# nyan-pirate.net
KiCad netlist of a schematic drawn in EAGLE
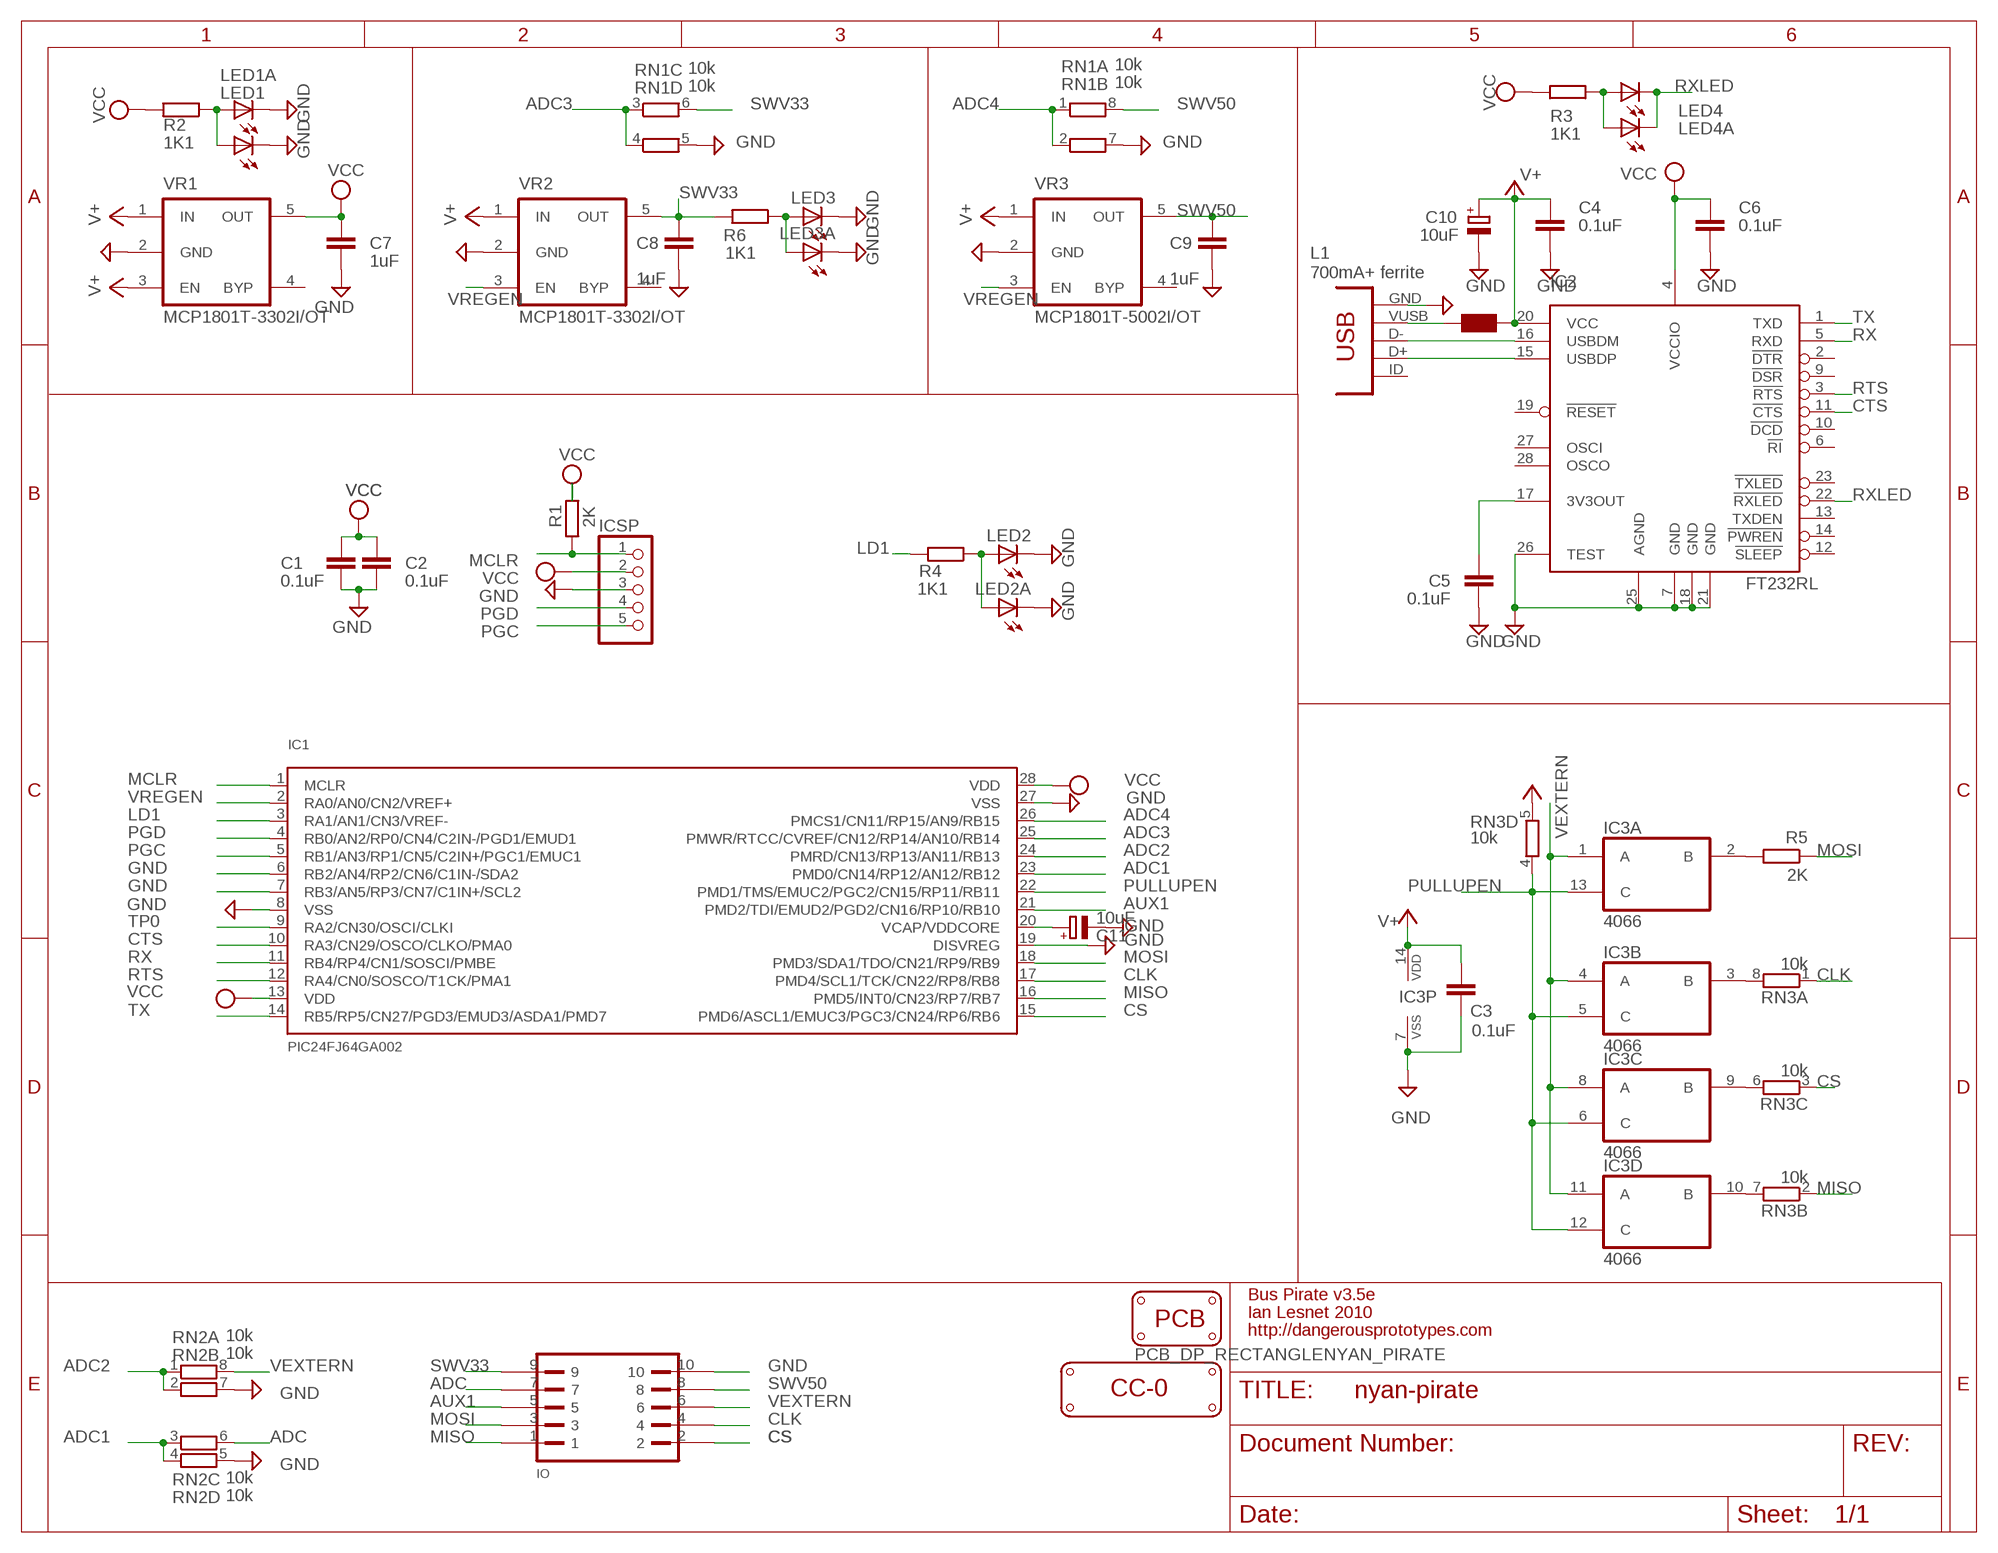
[diagram p0: schematic, sheet 1]

(export (version "E")
  (design (tool "Eeschema 10.0.6"))
  (components
    (comp (ref "C1")
      (value "0.1uF")
      (footprint "eagle-import:C603")
      (libsource (lib "eagle-import") (part "CAPC603"))
    )
    (comp (ref "C2")
      (value "0.1uF")
      (footprint "eagle-import:C603")
      (libsource (lib "eagle-import") (part "CAPC603"))
    )
    (comp (ref "C3")
      (value "0.1uF")
      (footprint "eagle-import:C603")
      (libsource (lib "eagle-import") (part "CAPC603"))
    )
    (comp (ref "C4")
      (value "0.1uF")
      (footprint "eagle-import:C603")
      (libsource (lib "eagle-import") (part "CAPC603"))
    )
    (comp (ref "C5")
      (value "0.1uF")
      (footprint "eagle-import:C603")
      (libsource (lib "eagle-import") (part "CAPC603"))
    )
    (comp (ref "C6")
      (value "0.1uF")
      (footprint "eagle-import:C603")
      (libsource (lib "eagle-import") (part "CAPC603"))
    )
    (comp (ref "C7")
      (value "1uF")
      (footprint "eagle-import:C603")
      (libsource (lib "eagle-import") (part "CAPC603"))
    )
    (comp (ref "C8")
      (value "1uF")
      (footprint "eagle-import:C603")
      (libsource (lib "eagle-import") (part "CAPC603"))
    )
    (comp (ref "C9")
      (value "1uF")
      (footprint "eagle-import:C603")
      (libsource (lib "eagle-import") (part "CAPC603"))
    )
    (comp (ref "C10")
      (value "10uF")
      (footprint "eagle-import:SMC_A")
      (libsource (lib "eagle-import") (part "CPOL-EUSMCA"))
    )
    (comp (ref "C11")
      (value "10uF")
      (footprint "eagle-import:SMC_A")
      (libsource (lib "eagle-import") (part "CPOL-EUSMCA"))
    )
    (comp (ref "IC1")
      (value "PIC24FJ64GA002")
      (footprint "eagle-import:SSOP28")
      (libsource (lib "eagle-import") (part "PIC24FJ64GA002"))
    )
    (comp (ref "IC2")
      (value "FT232RL")
      (footprint "eagle-import:SSOP28")
      (libsource (lib "eagle-import") (part "FT232RL"))
    )
    (comp (ref "IC3")
      (value "4066")
      (footprint "eagle-import:TSSOP14")
      (libsource (lib "eagle-import") (part "4066"))
    )
    (comp (ref "ICSP")
      (value "PINHD-1X5")
      (footprint "eagle-import:1X05")
      (libsource (lib "eagle-import") (part "PINHD-1X5"))
    )
    (comp (ref "IO")
      (value "HEADER2X5-SHRD-PTH-B")
      (footprint "eagle-import:PINSHRD_PTH_2X05B")
      (libsource (lib "eagle-import") (part "HEADER2X5-SHRD-PTH-B"))
    )
    (comp (ref "J1")
      (value "CON-USB-MINI-BUSB1")
      (footprint "eagle-import:CONN_USB_MINI-B")
      (libsource (lib "eagle-import") (part "CON-USB-MINI-BUSB1"))
    )
    (comp (ref "L1")
      (value "700mA+ ferrite")
      (footprint "eagle-import:WE-KI_0805_B")
      (libsource (lib "eagle-import") (part "WE-KIL_0805"))
    )
    (comp (ref "LED1")
      (value "LEDCHIP-LED0805")
      (footprint "eagle-import:CHIP-LED0805")
      (libsource (lib "eagle-import") (part "LEDCHIP-LED0805"))
    )
    (comp (ref "LED1A")
      (value "LEDCHIP-LED0805")
      (footprint "eagle-import:CHIP-LED0805")
      (libsource (lib "eagle-import") (part "LEDCHIP-LED0805"))
    )
    (comp (ref "LED2")
      (value "LEDCHIP-LED0805")
      (footprint "eagle-import:CHIP-LED0805")
      (libsource (lib "eagle-import") (part "LEDCHIP-LED0805"))
    )
    (comp (ref "LED2A")
      (value "LEDCHIP-LED0805")
      (footprint "eagle-import:CHIP-LED0805")
      (libsource (lib "eagle-import") (part "LEDCHIP-LED0805"))
    )
    (comp (ref "LED3")
      (value "LEDCHIP-LED0805")
      (footprint "eagle-import:CHIP-LED0805")
      (libsource (lib "eagle-import") (part "LEDCHIP-LED0805"))
    )
    (comp (ref "LED3A")
      (value "LEDCHIP-LED0805")
      (footprint "eagle-import:CHIP-LED0805")
      (libsource (lib "eagle-import") (part "LEDCHIP-LED0805"))
    )
    (comp (ref "LED4")
      (value "LEDCHIP-LED0805")
      (footprint "eagle-import:CHIP-LED0805")
      (libsource (lib "eagle-import") (part "LEDCHIP-LED0805"))
    )
    (comp (ref "LED4A")
      (value "LEDCHIP-LED0805")
      (footprint "eagle-import:CHIP-LED0805")
      (libsource (lib "eagle-import") (part "LEDCHIP-LED0805"))
    )
    (comp (ref "LOGO1")
      (value "LOGO_CC-0")
      (footprint "eagle-import:LOGO_CC-0")
      (libsource (lib "eagle-import") (part "LOGO_CC-0"))
    )
    (comp (ref "PCB1")
      (value "PCB_DP_RECTANGLENYAN_PIRATE")
      (footprint "eagle-import:NYAN_PIRATE")
      (libsource (lib "eagle-import") (part "PCB_DP_RECTANGLENYAN_PIRATE"))
    )
    (comp (ref "R1")
      (value "2K")
      (footprint "eagle-import:R603")
      (libsource (lib "eagle-import") (part "RESISTORR603"))
    )
    (comp (ref "R2")
      (value "1K1")
      (footprint "eagle-import:R603")
      (libsource (lib "eagle-import") (part "RESISTORR603"))
    )
    (comp (ref "R3")
      (value "1K1")
      (footprint "eagle-import:R603")
      (libsource (lib "eagle-import") (part "RESISTORR603"))
    )
    (comp (ref "R4")
      (value "1K1")
      (footprint "eagle-import:R603")
      (libsource (lib "eagle-import") (part "RESISTORR603"))
    )
    (comp (ref "R5")
      (value "2K")
      (footprint "eagle-import:R603")
      (libsource (lib "eagle-import") (part "RESISTORR603"))
    )
    (comp (ref "R6")
      (value "1K1")
      (footprint "eagle-import:R603")
      (libsource (lib "eagle-import") (part "RESISTORR603"))
    )
    (comp (ref "RN1")
      (value "10k")
      (footprint "eagle-import:RN8P-4R-CRA06S")
      (libsource (lib "eagle-import") (part "RNETWORK"))
    )
    (comp (ref "RN2")
      (value "10k")
      (footprint "eagle-import:RN8P-4R-CRA06S")
      (libsource (lib "eagle-import") (part "RNETWORK"))
    )
    (comp (ref "RN3")
      (value "10k")
      (footprint "eagle-import:RN8P-4R-CRA06S")
      (libsource (lib "eagle-import") (part "RNETWORK"))
    )
    (comp (ref "VR1")
      (value "MCP1801T-3302I/OT")
      (footprint "eagle-import:SOT-23-5")
      (libsource (lib "eagle-import") (part "MIC5205"))
    )
    (comp (ref "VR2")
      (value "MCP1801T-3302I/OT")
      (footprint "eagle-import:SOT-23-5")
      (libsource (lib "eagle-import") (part "MIC5205"))
    )
    (comp (ref "VR3")
      (value "MCP1801T-5002I/OT")
      (footprint "eagle-import:SOT-23-5")
      (libsource (lib "eagle-import") (part "MIC5205"))
    )
  )
  (nets
    (net (code "1") (name "/ADC") (class "Default")
      (node (ref "IO") (pin "7") (pinfunction "7_7") (pintype "passive"))
      (node (ref "RN2") (pin "6") (pinfunction "2_6") (pintype "passive"))
    )
    (net (code "2") (name "/ADC1") (class "Default")
      (node (ref "IC1") (pin "23") (pinfunction "PMD0/CN14/RP12/AN12/RB12_23") (pintype "bidirectional"))
      (node (ref "RN2") (pin "3") (pinfunction "1_3") (pintype "passive"))
      (node (ref "RN2") (pin "4") (pinfunction "1_4") (pintype "passive"))
    )
    (net (code "3") (name "/ADC2") (class "Default")
      (node (ref "IC1") (pin "24") (pinfunction "PMRD/CN13/RP13/AN11/RB13_24") (pintype "bidirectional"))
      (node (ref "RN2") (pin "1") (pinfunction "1_1") (pintype "passive"))
      (node (ref "RN2") (pin "2") (pinfunction "1_2") (pintype "passive"))
    )
    (net (code "4") (name "/ADC3") (class "Default")
      (node (ref "IC1") (pin "25") (pinfunction "PMWR/RTCC/CVREF/CN12/RP14/AN10/RB14_25") (pintype "bidirectional"))
      (node (ref "RN1") (pin "3") (pinfunction "1_3") (pintype "passive"))
      (node (ref "RN1") (pin "4") (pinfunction "1_4") (pintype "passive"))
    )
    (net (code "5") (name "/ADC4") (class "Default")
      (node (ref "IC1") (pin "26") (pinfunction "PMCS1/CN11/RP15/AN9/RB15_26") (pintype "bidirectional"))
      (node (ref "RN1") (pin "1") (pinfunction "1_1") (pintype "passive"))
      (node (ref "RN1") (pin "2") (pinfunction "1_2") (pintype "passive"))
    )
    (net (code "6") (name "/AUX1") (class "Default")
      (node (ref "IC1") (pin "21") (pinfunction "PMD2/TDI/EMUD2/PGD2/CN16/RP10/RB10_21") (pintype "bidirectional"))
      (node (ref "IO") (pin "5") (pinfunction "5_5") (pintype "passive"))
    )
    (net (code "7") (name "/CLK") (class "Default")
      (node (ref "IC1") (pin "17") (pinfunction "PMD4/SCL1/TCK/CN22/RP8/RB8_17") (pintype "bidirectional"))
      (node (ref "IO") (pin "4") (pinfunction "4_4") (pintype "passive"))
      (node (ref "RN3") (pin "1") (pinfunction "1_1") (pintype "passive"))
    )
    (net (code "8") (name "/CS") (class "Default")
      (node (ref "IC1") (pin "15") (pinfunction "PMD6/ASCL1/EMUC3/PGC3/CN24/RP6/RB6_15") (pintype "bidirectional"))
      (node (ref "IO") (pin "2") (pinfunction "2_2") (pintype "passive"))
      (node (ref "RN3") (pin "3") (pinfunction "1_3") (pintype "passive"))
    )
    (net (code "9") (name "/CTS") (class "Default")
      (node (ref "IC1") (pin "10") (pinfunction "RA3/CN29/OSCO/CLKO/PMA0_10") (pintype "bidirectional"))
      (node (ref "IC2") (pin "11") (pinfunction "~{CTS}_11") (pintype "bidirectional"))
    )
    (net (code "10") (name "/LD1") (class "Default")
      (node (ref "IC1") (pin "3") (pinfunction "RA1/AN1/CN3/VREF-_3") (pintype "bidirectional"))
      (node (ref "R4") (pin "2") (pinfunction "2_2") (pintype "passive"))
    )
    (net (code "11") (name "/MCLR") (class "Default")
      (node (ref "IC1") (pin "1") (pinfunction "MCLR_1") (pintype "input"))
      (node (ref "ICSP") (pin "1") (pinfunction "1_1") (pintype "passive"))
      (node (ref "R1") (pin "1") (pinfunction "1_1") (pintype "passive"))
    )
    (net (code "12") (name "/MISO") (class "Default")
      (node (ref "IC1") (pin "16") (pinfunction "PMD5/INT0/CN23/RP7/RB7_16") (pintype "bidirectional"))
      (node (ref "IO") (pin "1") (pinfunction "1_1") (pintype "passive"))
      (node (ref "RN3") (pin "2") (pinfunction "1_2") (pintype "passive"))
    )
    (net (code "13") (name "/MOSI") (class "Default")
      (node (ref "IC1") (pin "18") (pinfunction "PMD3/SDA1/TDO/CN21/RP9/RB9_18") (pintype "bidirectional"))
      (node (ref "IO") (pin "3") (pinfunction "3_3") (pintype "passive"))
      (node (ref "R5") (pin "1") (pinfunction "1_1") (pintype "passive"))
    )
    (net (code "14") (name "/PGC") (class "Default")
      (node (ref "IC1") (pin "5") (pinfunction "RB1/AN3/RP1/CN5/C2IN+/PGC1/EMUC1_5") (pintype "bidirectional"))
      (node (ref "ICSP") (pin "5") (pinfunction "5_5") (pintype "passive"))
    )
    (net (code "15") (name "/PGD") (class "Default")
      (node (ref "IC1") (pin "4") (pinfunction "RB0/AN2/RP0/CN4/C2IN-/PGD1/EMUD1_4") (pintype "bidirectional"))
      (node (ref "ICSP") (pin "4") (pinfunction "4_4") (pintype "passive"))
    )
    (net (code "16") (name "/PULLUPEN") (class "Default")
      (node (ref "IC1") (pin "22") (pinfunction "PMD1/TMS/EMUC2/PGC2/CN15/RP11/RB11_22") (pintype "bidirectional"))
      (node (ref "IC3") (pin "12") (pinfunction "C_12") (pintype "input"))
      (node (ref "IC3") (pin "13") (pinfunction "C_13") (pintype "input"))
      (node (ref "IC3") (pin "5") (pinfunction "C_5") (pintype "input"))
      (node (ref "IC3") (pin "6") (pinfunction "C_6") (pintype "input"))
      (node (ref "RN3") (pin "4") (pinfunction "1_4") (pintype "passive"))
    )
    (net (code "17") (name "/RTS") (class "Default")
      (node (ref "IC1") (pin "12") (pinfunction "RA4/CN0/SOSCO/T1CK/PMA1_12") (pintype "bidirectional"))
      (node (ref "IC2") (pin "3") (pinfunction "~{RTS}_3") (pintype "bidirectional"))
    )
    (net (code "18") (name "/RX") (class "Default")
      (node (ref "IC1") (pin "11") (pinfunction "RB4/RP4/CN1/SOSCI/PMBE_11") (pintype "bidirectional"))
      (node (ref "IC2") (pin "5") (pinfunction "RXD_5") (pintype "bidirectional"))
    )
    (net (code "19") (name "/RXLED") (class "Default")
      (node (ref "IC2") (pin "22") (pinfunction "~{RXLED}_22") (pintype "bidirectional"))
      (node (ref "LED4") (pin "C") (pinfunction "C_C") (pintype "passive"))
      (node (ref "LED4A") (pin "C") (pinfunction "C_C") (pintype "passive"))
    )
    (net (code "20") (name "/SWV33") (class "Default")
      (node (ref "C8") (pin "1") (pinfunction "1_1") (pintype "passive"))
      (node (ref "IO") (pin "9") (pinfunction "9_9") (pintype "passive"))
      (node (ref "R6") (pin "2") (pinfunction "2_2") (pintype "passive"))
      (node (ref "RN1") (pin "6") (pinfunction "2_6") (pintype "passive"))
      (node (ref "VR2") (pin "5") (pinfunction "OUT_5") (pintype "bidirectional"))
    )
    (net (code "21") (name "/SWV50") (class "Default")
      (node (ref "C9") (pin "1") (pinfunction "1_1") (pintype "passive"))
      (node (ref "IO") (pin "8") (pinfunction "8_8") (pintype "passive"))
      (node (ref "RN1") (pin "8") (pinfunction "2_8") (pintype "passive"))
      (node (ref "VR3") (pin "5") (pinfunction "OUT_5") (pintype "bidirectional"))
    )
    (net (code "22") (name "/TP0") (class "Default")
      (node (ref "IC1") (pin "9") (pinfunction "RA2/CN30/OSCI/CLKI_9") (pintype "bidirectional"))
    )
    (net (code "23") (name "/TX") (class "Default")
      (node (ref "IC1") (pin "14") (pinfunction "RB5/RP5/CN27/PGD3/EMUD3/ASDA1/PMD7_14") (pintype "bidirectional"))
      (node (ref "IC2") (pin "1") (pinfunction "TXD_1") (pintype "bidirectional"))
    )
    (net (code "24") (name "/VEXTERN") (class "Default")
      (node (ref "IC3") (pin "1") (pinfunction "A_1") (pintype "tri_state"))
      (node (ref "IC3") (pin "11") (pinfunction "A_11") (pintype "tri_state"))
      (node (ref "IC3") (pin "4") (pinfunction "A_4") (pintype "tri_state"))
      (node (ref "IC3") (pin "8") (pinfunction "A_8") (pintype "tri_state"))
      (node (ref "IO") (pin "6") (pinfunction "6_6") (pintype "passive"))
      (node (ref "RN2") (pin "8") (pinfunction "2_8") (pintype "passive"))
    )
    (net (code "25") (name "/VREGEN") (class "Default")
      (node (ref "IC1") (pin "2") (pinfunction "RA0/AN0/CN2/VREF+_2") (pintype "bidirectional"))
      (node (ref "VR2") (pin "3") (pinfunction "EN_3") (pintype "bidirectional"))
      (node (ref "VR3") (pin "3") (pinfunction "EN_3") (pintype "bidirectional"))
    )
    (net (code "26") (name "GND") (class "Default")
      (node (ref "C1") (pin "2") (pinfunction "2_2") (pintype "passive"))
      (node (ref "C10") (pin "-") (pinfunction "-_-") (pintype "passive"))
      (node (ref "C11") (pin "-") (pinfunction "-_-") (pintype "passive"))
      (node (ref "C2") (pin "2") (pinfunction "2_2") (pintype "passive"))
      (node (ref "C3") (pin "2") (pinfunction "2_2") (pintype "passive"))
      (node (ref "C4") (pin "2") (pinfunction "2_2") (pintype "passive"))
      (node (ref "C5") (pin "2") (pinfunction "2_2") (pintype "passive"))
      (node (ref "C6") (pin "2") (pinfunction "2_2") (pintype "passive"))
      (node (ref "C7") (pin "2") (pinfunction "2_2") (pintype "passive"))
      (node (ref "C8") (pin "2") (pinfunction "2_2") (pintype "passive"))
      (node (ref "C9") (pin "2") (pinfunction "2_2") (pintype "passive"))
      (node (ref "IC1") (pin "19") (pinfunction "DISVREG_19") (pintype "power_in"))
      (node (ref "IC1") (pin "27") (pinfunction "VSS_27") (pintype "power_in"))
      (node (ref "IC1") (pin "6") (pinfunction "RB2/AN4/RP2/CN6/C1IN-/SDA2_6") (pintype "bidirectional"))
      (node (ref "IC1") (pin "7") (pinfunction "RB3/AN5/RP3/CN7/C1IN+/SCL2_7") (pintype "bidirectional"))
      (node (ref "IC1") (pin "8") (pinfunction "VSS_8") (pintype "power_in"))
      (node (ref "IC2") (pin "18") (pinfunction "GND_18") (pintype "bidirectional"))
      (node (ref "IC2") (pin "21") (pinfunction "GND_21") (pintype "bidirectional"))
      (node (ref "IC2") (pin "25") (pinfunction "AGND_25") (pintype "bidirectional"))
      (node (ref "IC2") (pin "26") (pinfunction "TEST_26") (pintype "bidirectional"))
      (node (ref "IC2") (pin "7") (pinfunction "GND_7") (pintype "bidirectional"))
      (node (ref "IC3") (pin "7") (pinfunction "VSS_7") (pintype "power_in"))
      (node (ref "ICSP") (pin "3") (pinfunction "3_3") (pintype "passive"))
      (node (ref "IO") (pin "10") (pinfunction "10_10") (pintype "passive"))
      (node (ref "J1") (pin "GND") (pinfunction "GND_GND") (pintype "bidirectional"))
      (node (ref "LED1") (pin "C") (pinfunction "C_C") (pintype "passive"))
      (node (ref "LED1A") (pin "C") (pinfunction "C_C") (pintype "passive"))
      (node (ref "LED2") (pin "C") (pinfunction "C_C") (pintype "passive"))
      (node (ref "LED2A") (pin "C") (pinfunction "C_C") (pintype "passive"))
      (node (ref "LED3") (pin "C") (pinfunction "C_C") (pintype "passive"))
      (node (ref "LED3A") (pin "C") (pinfunction "C_C") (pintype "passive"))
      (node (ref "RN1") (pin "5") (pinfunction "2_5") (pintype "passive"))
      (node (ref "RN1") (pin "7") (pinfunction "2_7") (pintype "passive"))
      (node (ref "RN2") (pin "5") (pinfunction "2_5") (pintype "passive"))
      (node (ref "RN2") (pin "7") (pinfunction "2_7") (pintype "passive"))
      (node (ref "VR1") (pin "2") (pinfunction "GND_2") (pintype "bidirectional"))
      (node (ref "VR2") (pin "2") (pinfunction "GND_2") (pintype "bidirectional"))
      (node (ref "VR3") (pin "2") (pinfunction "GND_2") (pintype "bidirectional"))
    )
    (net (code "27") (name "Net-(IC1-VCAP{slash}VDDCORE)") (class "Default")
      (node (ref "C11") (pin "+") (pinfunction "+_+") (pintype "passive"))
      (node (ref "IC1") (pin "20") (pinfunction "VCAP/VDDCORE_20") (pintype "power_in"))
    )
    (net (code "28") (name "Net-(IC2-3V3OUT)") (class "Default")
      (node (ref "C5") (pin "1") (pinfunction "1_1") (pintype "passive"))
      (node (ref "IC2") (pin "17") (pinfunction "3V3OUT_17") (pintype "bidirectional"))
    )
    (net (code "29") (name "Net-(IC2-USBDM)") (class "Default")
      (node (ref "IC2") (pin "16") (pinfunction "USBDM_16") (pintype "bidirectional"))
      (node (ref "J1") (pin "D-") (pinfunction "D-_D-") (pintype "bidirectional"))
    )
    (net (code "30") (name "Net-(IC2-USBDP)") (class "Default")
      (node (ref "IC2") (pin "15") (pinfunction "USBDP_15") (pintype "bidirectional"))
      (node (ref "J1") (pin "D+") (pinfunction "D+_D+") (pintype "bidirectional"))
    )
    (net (code "31") (name "Net-(IC3A-B)") (class "Default")
      (node (ref "IC3") (pin "2") (pinfunction "B_2") (pintype "tri_state"))
      (node (ref "R5") (pin "2") (pinfunction "2_2") (pintype "passive"))
    )
    (net (code "32") (name "Net-(IC3B-B)") (class "Default")
      (node (ref "IC3") (pin "3") (pinfunction "B_3") (pintype "tri_state"))
      (node (ref "RN3") (pin "8") (pinfunction "2_8") (pintype "passive"))
    )
    (net (code "33") (name "Net-(IC3C-B)") (class "Default")
      (node (ref "IC3") (pin "9") (pinfunction "B_9") (pintype "tri_state"))
      (node (ref "RN3") (pin "6") (pinfunction "2_6") (pintype "passive"))
    )
    (net (code "34") (name "Net-(IC3D-B)") (class "Default")
      (node (ref "IC3") (pin "10") (pinfunction "B_10") (pintype "tri_state"))
      (node (ref "RN3") (pin "7") (pinfunction "2_7") (pintype "passive"))
    )
    (net (code "35") (name "Net-(L1-1)") (class "Default")
      (node (ref "J1") (pin "VUSB") (pinfunction "VUSB_VUSB") (pintype "bidirectional"))
      (node (ref "L1") (pin "2") (pinfunction "1_2") (pintype "passive"))
    )
    (net (code "36") (name "Net-(LED1-PadA)") (class "Default")
      (node (ref "LED1") (pin "A") (pinfunction "A_A") (pintype "passive"))
      (node (ref "LED1A") (pin "A") (pinfunction "A_A") (pintype "passive"))
      (node (ref "R2") (pin "1") (pinfunction "1_1") (pintype "passive"))
    )
    (net (code "37") (name "Net-(LED2-PadA)") (class "Default")
      (node (ref "LED2") (pin "A") (pinfunction "A_A") (pintype "passive"))
      (node (ref "LED2A") (pin "A") (pinfunction "A_A") (pintype "passive"))
      (node (ref "R4") (pin "1") (pinfunction "1_1") (pintype "passive"))
    )
    (net (code "38") (name "Net-(LED3-PadA)") (class "Default")
      (node (ref "LED3") (pin "A") (pinfunction "A_A") (pintype "passive"))
      (node (ref "LED3A") (pin "A") (pinfunction "A_A") (pintype "passive"))
      (node (ref "R6") (pin "1") (pinfunction "1_1") (pintype "passive"))
    )
    (net (code "39") (name "Net-(LED4-PadA)") (class "Default")
      (node (ref "LED4") (pin "A") (pinfunction "A_A") (pintype "passive"))
      (node (ref "LED4A") (pin "A") (pinfunction "A_A") (pintype "passive"))
      (node (ref "R3") (pin "1") (pinfunction "1_1") (pintype "passive"))
    )
    (net (code "40") (name "V+") (class "Default")
      (node (ref "C10") (pin "+") (pinfunction "+_+") (pintype "passive"))
      (node (ref "C3") (pin "1") (pinfunction "1_1") (pintype "passive"))
      (node (ref "C4") (pin "1") (pinfunction "1_1") (pintype "passive"))
      (node (ref "IC2") (pin "20") (pinfunction "VCC_20") (pintype "bidirectional"))
      (node (ref "IC3") (pin "14") (pinfunction "VDD_14") (pintype "power_in"))
      (node (ref "L1") (pin "1") (pinfunction "2_1") (pintype "passive"))
      (node (ref "RN3") (pin "5") (pinfunction "2_5") (pintype "passive"))
      (node (ref "VR1") (pin "1") (pinfunction "IN_1") (pintype "bidirectional"))
      (node (ref "VR1") (pin "3") (pinfunction "EN_3") (pintype "bidirectional"))
      (node (ref "VR2") (pin "1") (pinfunction "IN_1") (pintype "bidirectional"))
      (node (ref "VR3") (pin "1") (pinfunction "IN_1") (pintype "bidirectional"))
    )
    (net (code "41") (name "VCC") (class "Default")
      (node (ref "C1") (pin "1") (pinfunction "1_1") (pintype "passive"))
      (node (ref "C2") (pin "1") (pinfunction "1_1") (pintype "passive"))
      (node (ref "C6") (pin "1") (pinfunction "1_1") (pintype "passive"))
      (node (ref "C7") (pin "1") (pinfunction "1_1") (pintype "passive"))
      (node (ref "IC1") (pin "13") (pinfunction "VDD_13") (pintype "power_in"))
      (node (ref "IC1") (pin "28") (pinfunction "VDD_28") (pintype "power_in"))
      (node (ref "IC2") (pin "4") (pinfunction "VCCIO_4") (pintype "bidirectional"))
      (node (ref "ICSP") (pin "2") (pinfunction "2_2") (pintype "passive"))
      (node (ref "R1") (pin "2") (pinfunction "2_2") (pintype "passive"))
      (node (ref "R2") (pin "2") (pinfunction "2_2") (pintype "passive"))
      (node (ref "R3") (pin "2") (pinfunction "2_2") (pintype "passive"))
      (node (ref "VR1") (pin "5") (pinfunction "OUT_5") (pintype "bidirectional"))
    )
    (net (code "42") (name "unconnected-(IC2-OSCI-Pad27)") (class "Default")
      (node (ref "IC2") (pin "27") (pinfunction "OSCI_27") (pintype "bidirectional"))
    )
    (net (code "43") (name "unconnected-(IC2-OSCO-Pad28)") (class "Default")
      (node (ref "IC2") (pin "28") (pinfunction "OSCO_28") (pintype "bidirectional"))
    )
    (net (code "44") (name "unconnected-(IC2-TXDEN-Pad13)") (class "Default")
      (node (ref "IC2") (pin "13") (pinfunction "TXDEN_13") (pintype "bidirectional"))
    )
    (net (code "45") (name "unconnected-(IC2-~{DCD}-Pad10)") (class "Default")
      (node (ref "IC2") (pin "10") (pinfunction "~{DCD}_10") (pintype "bidirectional"))
    )
    (net (code "46") (name "unconnected-(IC2-~{DSR}-Pad9)") (class "Default")
      (node (ref "IC2") (pin "9") (pinfunction "~{DSR}_9") (pintype "bidirectional"))
    )
    (net (code "47") (name "unconnected-(IC2-~{DTR}-Pad2)") (class "Default")
      (node (ref "IC2") (pin "2") (pinfunction "~{DTR}_2") (pintype "bidirectional"))
    )
    (net (code "48") (name "unconnected-(IC2-~{PWREN}-Pad14)") (class "Default")
      (node (ref "IC2") (pin "14") (pinfunction "~{PWREN}_14") (pintype "bidirectional"))
    )
    (net (code "49") (name "unconnected-(IC2-~{RESET}-Pad19)") (class "Default")
      (node (ref "IC2") (pin "19") (pinfunction "~{RESET}_19") (pintype "bidirectional"))
    )
    (net (code "50") (name "unconnected-(IC2-~{RI}-Pad6)") (class "Default")
      (node (ref "IC2") (pin "6") (pinfunction "~{RI}_6") (pintype "bidirectional"))
    )
    (net (code "51") (name "unconnected-(IC2-~{SLEEP}-Pad12)") (class "Default")
      (node (ref "IC2") (pin "12") (pinfunction "~{SLEEP}_12") (pintype "bidirectional"))
    )
    (net (code "52") (name "unconnected-(IC2-~{TXLED}-Pad23)") (class "Default")
      (node (ref "IC2") (pin "23") (pinfunction "~{TXLED}_23") (pintype "bidirectional"))
    )
    (net (code "53") (name "unconnected-(J1B-USBID-PadID)") (class "Default")
      (node (ref "J1") (pin "ID") (pinfunction "USBID_ID") (pintype "bidirectional"))
    )
    (net (code "54") (name "unconnected-(VR1-BYP-Pad4)") (class "Default")
      (node (ref "VR1") (pin "4") (pinfunction "BYP_4") (pintype "bidirectional"))
    )
    (net (code "55") (name "unconnected-(VR2-BYP-Pad4)") (class "Default")
      (node (ref "VR2") (pin "4") (pinfunction "BYP_4") (pintype "bidirectional"))
    )
    (net (code "56") (name "unconnected-(VR3-BYP-Pad4)") (class "Default")
      (node (ref "VR3") (pin "4") (pinfunction "BYP_4") (pintype "bidirectional"))
    )
  )
)
